# AmpBoardSchematic.net
KiCad netlist of a schematic drawn in EAGLE
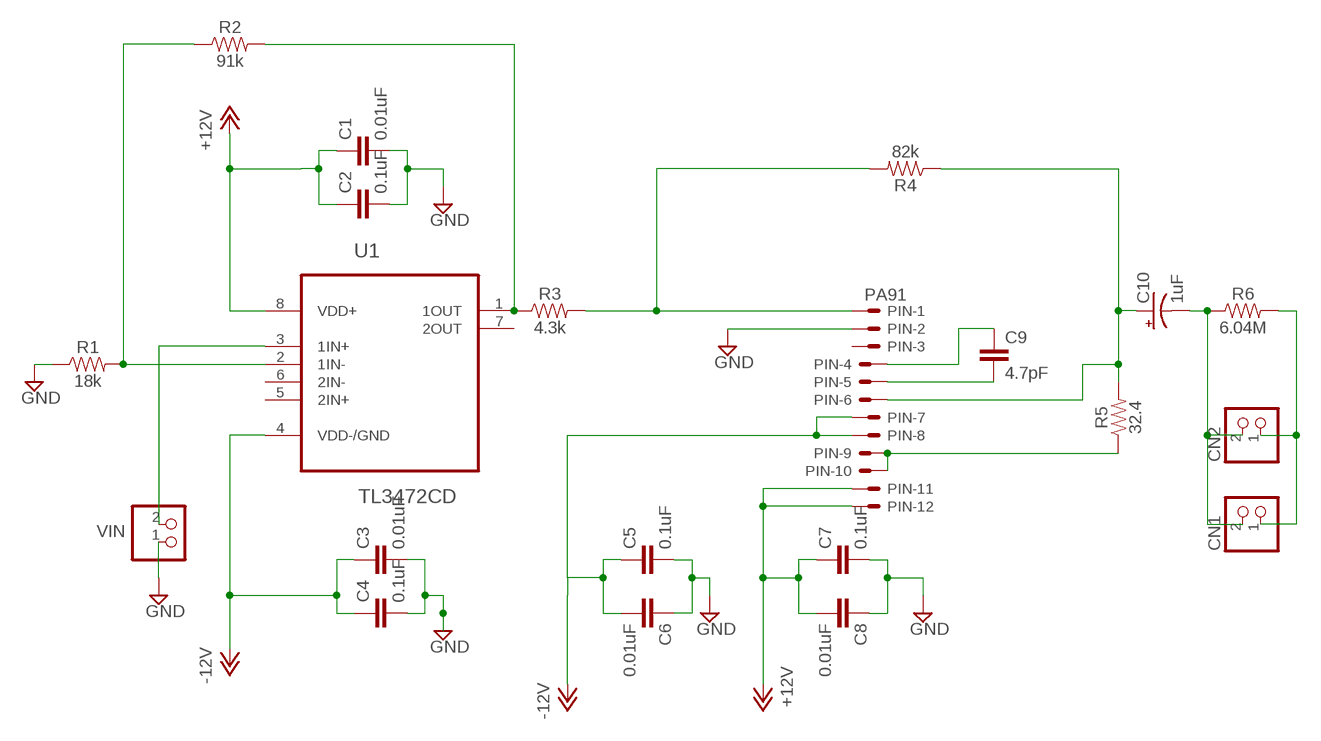
[diagram p0: schematic, sheet 1]

(export (version "E")
  (design (tool "Eeschema 10.0.6"))
  (components
    (comp (ref "C1")
      (value "0.01uF")
      (footprint "eagle-import:RESC0805_M")
      (fields (field (name "MF") "KEMET") (field (name "MPN") "C0805C103K1RACTU"))
      (libsource (lib "eagle-import") (part "CAPACITOR_0805_M"))
    )
    (comp (ref "C2")
      (value "0.1uF")
      (footprint "eagle-import:RESC0805_M")
      (fields (field (name "MF") "AVX") (field (name "MPN") "08055C104KAT2A"))
      (libsource (lib "eagle-import") (part "CAPACITOR_0805_M"))
    )
    (comp (ref "C3")
      (value "0.01uF")
      (footprint "eagle-import:RESC0805_M")
      (fields (field (name "MF") "KEMET") (field (name "MPN") "C0805C103K1RACTU"))
      (libsource (lib "eagle-import") (part "CAPACITOR_0805_M"))
    )
    (comp (ref "C4")
      (value "0.1uF")
      (footprint "eagle-import:RESC0805_M")
      (fields (field (name "MF") "AVX") (field (name "MPN") "08055C104KAT2A"))
      (libsource (lib "eagle-import") (part "CAPACITOR_0805_M"))
    )
    (comp (ref "C5")
      (value "0.1uF")
      (footprint "eagle-import:RESC0805_M")
      (fields (field (name "MF") "AVX") (field (name "MPN") "08055C104KAT2A"))
      (libsource (lib "eagle-import") (part "CAPACITOR_0805_M"))
    )
    (comp (ref "C6")
      (value "0.01uF")
      (footprint "eagle-import:RESC0805_M")
      (fields (field (name "MF") "KEMET") (field (name "MPN") "C0805C103K1RACTU"))
      (libsource (lib "eagle-import") (part "CAPACITOR_0805_M"))
    )
    (comp (ref "C7")
      (value "0.1uF")
      (footprint "eagle-import:RESC0805_M")
      (fields (field (name "MF") "AVX") (field (name "MPN") "08055C104KAT2A"))
      (libsource (lib "eagle-import") (part "CAPACITOR_0805_M"))
    )
    (comp (ref "C8")
      (value "0.01uF")
      (footprint "eagle-import:RESC0805_M")
      (fields (field (name "MF") "KEMET") (field (name "MPN") "C0805C103K1RACTU"))
      (libsource (lib "eagle-import") (part "CAPACITOR_0805_M"))
    )
    (comp (ref "C9")
      (value "4.7pF")
      (footprint "eagle-import:RESC0805_M")
      (fields (field (name "MF") "KEMET") (field (name "MPN") "C0805C479C5GACTU"))
      (libsource (lib "eagle-import") (part "CAPACITOR_0805_M"))
    )
    (comp (ref "C10")
      (value "1uF")
      (footprint "eagle-import:085CS_1AR")
      (fields (field (name "MF") "AVX") (field (name "MPN") "06035A102JAT2A"))
      (libsource (lib "eagle-import") (part "CPOL-US085CS-1AR"))
    )
    (comp (ref "CN1")
      (value "JST_2PIN-THM")
      (footprint "eagle-import:JST-PH-2-THM")
      (libsource (lib "eagle-import") (part "JST_2PIN-THM"))
    )
    (comp (ref "CN2")
      (value "JST_2PIN-THM")
      (footprint "eagle-import:JST-PH-2-THM")
      (libsource (lib "eagle-import") (part "JST_2PIN-THM"))
    )
    (comp (ref "PIN")
      (value "PA91")
      (footprint "eagle-import:22-23-2121")
      (fields
        (field (name "MF") "MOLEX")
        (field (name "MPN") "22-23-2121")
        (field (name "OC_FARNELL") "unknown")
      )
      (libsource (lib "eagle-import") (part "22-23-2121"))
    )
    (comp (ref "R1")
      (value "18k")
      (footprint "eagle-import:0805")
      (fields (field (name "MF") "WELWYN") (field (name "MPN") "WCR0805-18KFI"))
      (libsource (lib "eagle-import") (part "RESISTOR0805"))
    )
    (comp (ref "R2")
      (value "91k")
      (footprint "eagle-import:0805")
      (fields (field (name "MF") "KOA SPEAR ELECTRONICS") (field (name "MPN") "SG73S2ATTD9102F"))
      (libsource (lib "eagle-import") (part "RESISTOR0805"))
    )
    (comp (ref "R3")
      (value "4.3k")
      (footprint "eagle-import:0805")
      (fields (field (name "MF") "VISHAY") (field (name "MPN") "CRCW08054K30FKEA"))
      (libsource (lib "eagle-import") (part "RESISTOR0805"))
    )
    (comp (ref "R4")
      (value "82k")
      (footprint "eagle-import:0805")
      (fields (field (name "MF") "WELWYN") (field (name "MPN") "WCR0805-82KFI"))
      (libsource (lib "eagle-import") (part "RESISTOR0805"))
    )
    (comp (ref "R5")
      (value "32.4")
      (footprint "eagle-import:0805")
      (fields (field (name "MF") "TE CONNECTIVITY") (field (name "MPN") "RN73C2A32K4BTDF"))
      (libsource (lib "eagle-import") (part "RESISTOR0805"))
    )
    (comp (ref "R6")
      (value "6.04M")
      (footprint "eagle-import:0805")
      (fields (field (name "MF") "VISHAY") (field (name "MPN") "CRCW08056M04FKEA."))
      (libsource (lib "eagle-import") (part "RESISTOR0805"))
    )
    (comp (ref "U1")
      (value "TL3472CD")
      (footprint "eagle-import:SOIC127P600X175-8N")
      (fields (field (name "MF") "Texas Instruments"))
      (libsource (lib "eagle-import") (part "TL3472CD"))
    )
    (comp (ref "VIN")
      (value "JST_2PIN-THM")
      (footprint "eagle-import:JST-PH-2-THM")
      (libsource (lib "eagle-import") (part "JST_2PIN-THM"))
    )
  )
  (nets
    (net (code "1") (name "+12V") (class "Default")
      (node (ref "C1") (pin "1") (pinfunction "1_1") (pintype "passive"))
      (node (ref "C2") (pin "1") (pinfunction "1_1") (pintype "passive"))
      (node (ref "C7") (pin "1") (pinfunction "1_1") (pintype "passive"))
      (node (ref "C8") (pin "2") (pinfunction "2_2") (pintype "passive"))
      (node (ref "PIN") (pin "11") (pinfunction "S_11") (pintype "passive"))
      (node (ref "PIN") (pin "12") (pinfunction "S_12") (pintype "passive"))
      (node (ref "U1") (pin "8") (pinfunction "VDD+_8") (pintype "power_in"))
    )
    (net (code "2") (name "-12V") (class "Default")
      (node (ref "C3") (pin "1") (pinfunction "1_1") (pintype "passive"))
      (node (ref "C4") (pin "1") (pinfunction "1_1") (pintype "passive"))
      (node (ref "C5") (pin "1") (pinfunction "1_1") (pintype "passive"))
      (node (ref "C6") (pin "2") (pinfunction "2_2") (pintype "passive"))
      (node (ref "PIN") (pin "7") (pinfunction "S_7") (pintype "passive"))
      (node (ref "PIN") (pin "8") (pinfunction "S_8") (pintype "passive"))
      (node (ref "U1") (pin "4") (pinfunction "VDD-/GND_4") (pintype "power_in"))
    )
    (net (code "3") (name "GND") (class "Default")
      (node (ref "C1") (pin "2") (pinfunction "2_2") (pintype "passive"))
      (node (ref "C2") (pin "2") (pinfunction "2_2") (pintype "passive"))
      (node (ref "C3") (pin "2") (pinfunction "2_2") (pintype "passive"))
      (node (ref "C4") (pin "2") (pinfunction "2_2") (pintype "passive"))
      (node (ref "C5") (pin "2") (pinfunction "2_2") (pintype "passive"))
      (node (ref "C6") (pin "1") (pinfunction "1_1") (pintype "passive"))
      (node (ref "C7") (pin "2") (pinfunction "2_2") (pintype "passive"))
      (node (ref "C8") (pin "1") (pinfunction "1_1") (pintype "passive"))
      (node (ref "PIN") (pin "2") (pinfunction "S_2") (pintype "passive"))
      (node (ref "R1") (pin "1") (pinfunction "1_1") (pintype "passive"))
      (node (ref "VIN") (pin "1") (pinfunction "2_1") (pintype "passive"))
    )
    (net (code "4") (name "Net-(CN1-1)") (class "Default")
      (node (ref "C10") (pin "-") (pinfunction "-_-") (pintype "passive"))
      (node (ref "CN1") (pin "2") (pinfunction "1_2") (pintype "passive"))
      (node (ref "CN2") (pin "2") (pinfunction "1_2") (pintype "passive"))
      (node (ref "R6") (pin "1") (pinfunction "1_1") (pintype "passive"))
    )
    (net (code "5") (name "Net-(CN1-2)") (class "Default")
      (node (ref "CN1") (pin "1") (pinfunction "2_1") (pintype "passive"))
      (node (ref "CN2") (pin "1") (pinfunction "2_1") (pintype "passive"))
      (node (ref "R6") (pin "2") (pinfunction "2_2") (pintype "passive"))
    )
    (net (code "6") (name "Net-(PINA-S)") (class "Default")
      (node (ref "PIN") (pin "1") (pinfunction "S_1") (pintype "passive"))
      (node (ref "R3") (pin "2") (pinfunction "2_2") (pintype "passive"))
      (node (ref "R4") (pin "2") (pinfunction "2_2") (pintype "passive"))
    )
    (net (code "7") (name "Net-(PINB-S)") (class "Default")
      (node (ref "PIN") (pin "10") (pinfunction "S_10") (pintype "passive"))
      (node (ref "PIN") (pin "9") (pinfunction "S_9") (pintype "passive"))
      (node (ref "R5") (pin "1") (pinfunction "1_1") (pintype "passive"))
    )
    (net (code "8") (name "Net-(PING-S)") (class "Default")
      (node (ref "C9") (pin "1") (pinfunction "1_1") (pintype "passive"))
      (node (ref "PIN") (pin "4") (pinfunction "S_4") (pintype "passive"))
    )
    (net (code "9") (name "Net-(PINH-S)") (class "Default")
      (node (ref "C9") (pin "2") (pinfunction "2_2") (pintype "passive"))
      (node (ref "PIN") (pin "5") (pinfunction "S_5") (pintype "passive"))
    )
    (net (code "10") (name "Net-(PINI-S)") (class "Default")
      (node (ref "C10") (pin "+") (pinfunction "+_+") (pintype "passive"))
      (node (ref "PIN") (pin "6") (pinfunction "S_6") (pintype "passive"))
      (node (ref "R4") (pin "1") (pinfunction "1_1") (pintype "passive"))
      (node (ref "R5") (pin "2") (pinfunction "2_2") (pintype "passive"))
    )
    (net (code "11") (name "Net-(U1-1IN+)") (class "Default")
      (node (ref "U1") (pin "3") (pinfunction "1IN+_3") (pintype "input"))
      (node (ref "VIN") (pin "2") (pinfunction "1_2") (pintype "passive"))
    )
    (net (code "12") (name "Net-(U1-1IN-)") (class "Default")
      (node (ref "R1") (pin "2") (pinfunction "2_2") (pintype "passive"))
      (node (ref "R2") (pin "1") (pinfunction "1_1") (pintype "passive"))
      (node (ref "U1") (pin "2") (pinfunction "1IN-_2") (pintype "input"))
    )
    (net (code "13") (name "Net-(U1-1OUT)") (class "Default")
      (node (ref "R2") (pin "2") (pinfunction "2_2") (pintype "passive"))
      (node (ref "R3") (pin "1") (pinfunction "1_1") (pintype "passive"))
      (node (ref "U1") (pin "1") (pinfunction "1OUT_1") (pintype "output"))
    )
    (net (code "14") (name "unconnected-(PINF-S-Pad3)") (class "Default")
      (node (ref "PIN") (pin "3") (pinfunction "S_3") (pintype "passive"))
    )
    (net (code "15") (name "unconnected-(U1-2IN+-Pad5)") (class "Default")
      (node (ref "U1") (pin "5") (pinfunction "2IN+_5") (pintype "input"))
    )
    (net (code "16") (name "unconnected-(U1-2IN--Pad6)") (class "Default")
      (node (ref "U1") (pin "6") (pinfunction "2IN-_6") (pintype "input"))
    )
    (net (code "17") (name "unconnected-(U1-2OUT-Pad7)") (class "Default")
      (node (ref "U1") (pin "7") (pinfunction "2OUT_7") (pintype "output"))
    )
  )
)
